# MACH_LOC_NUOC_KAROFI_V3_271015.net
KiCad netlist of a schematic drawn in Altium Designer
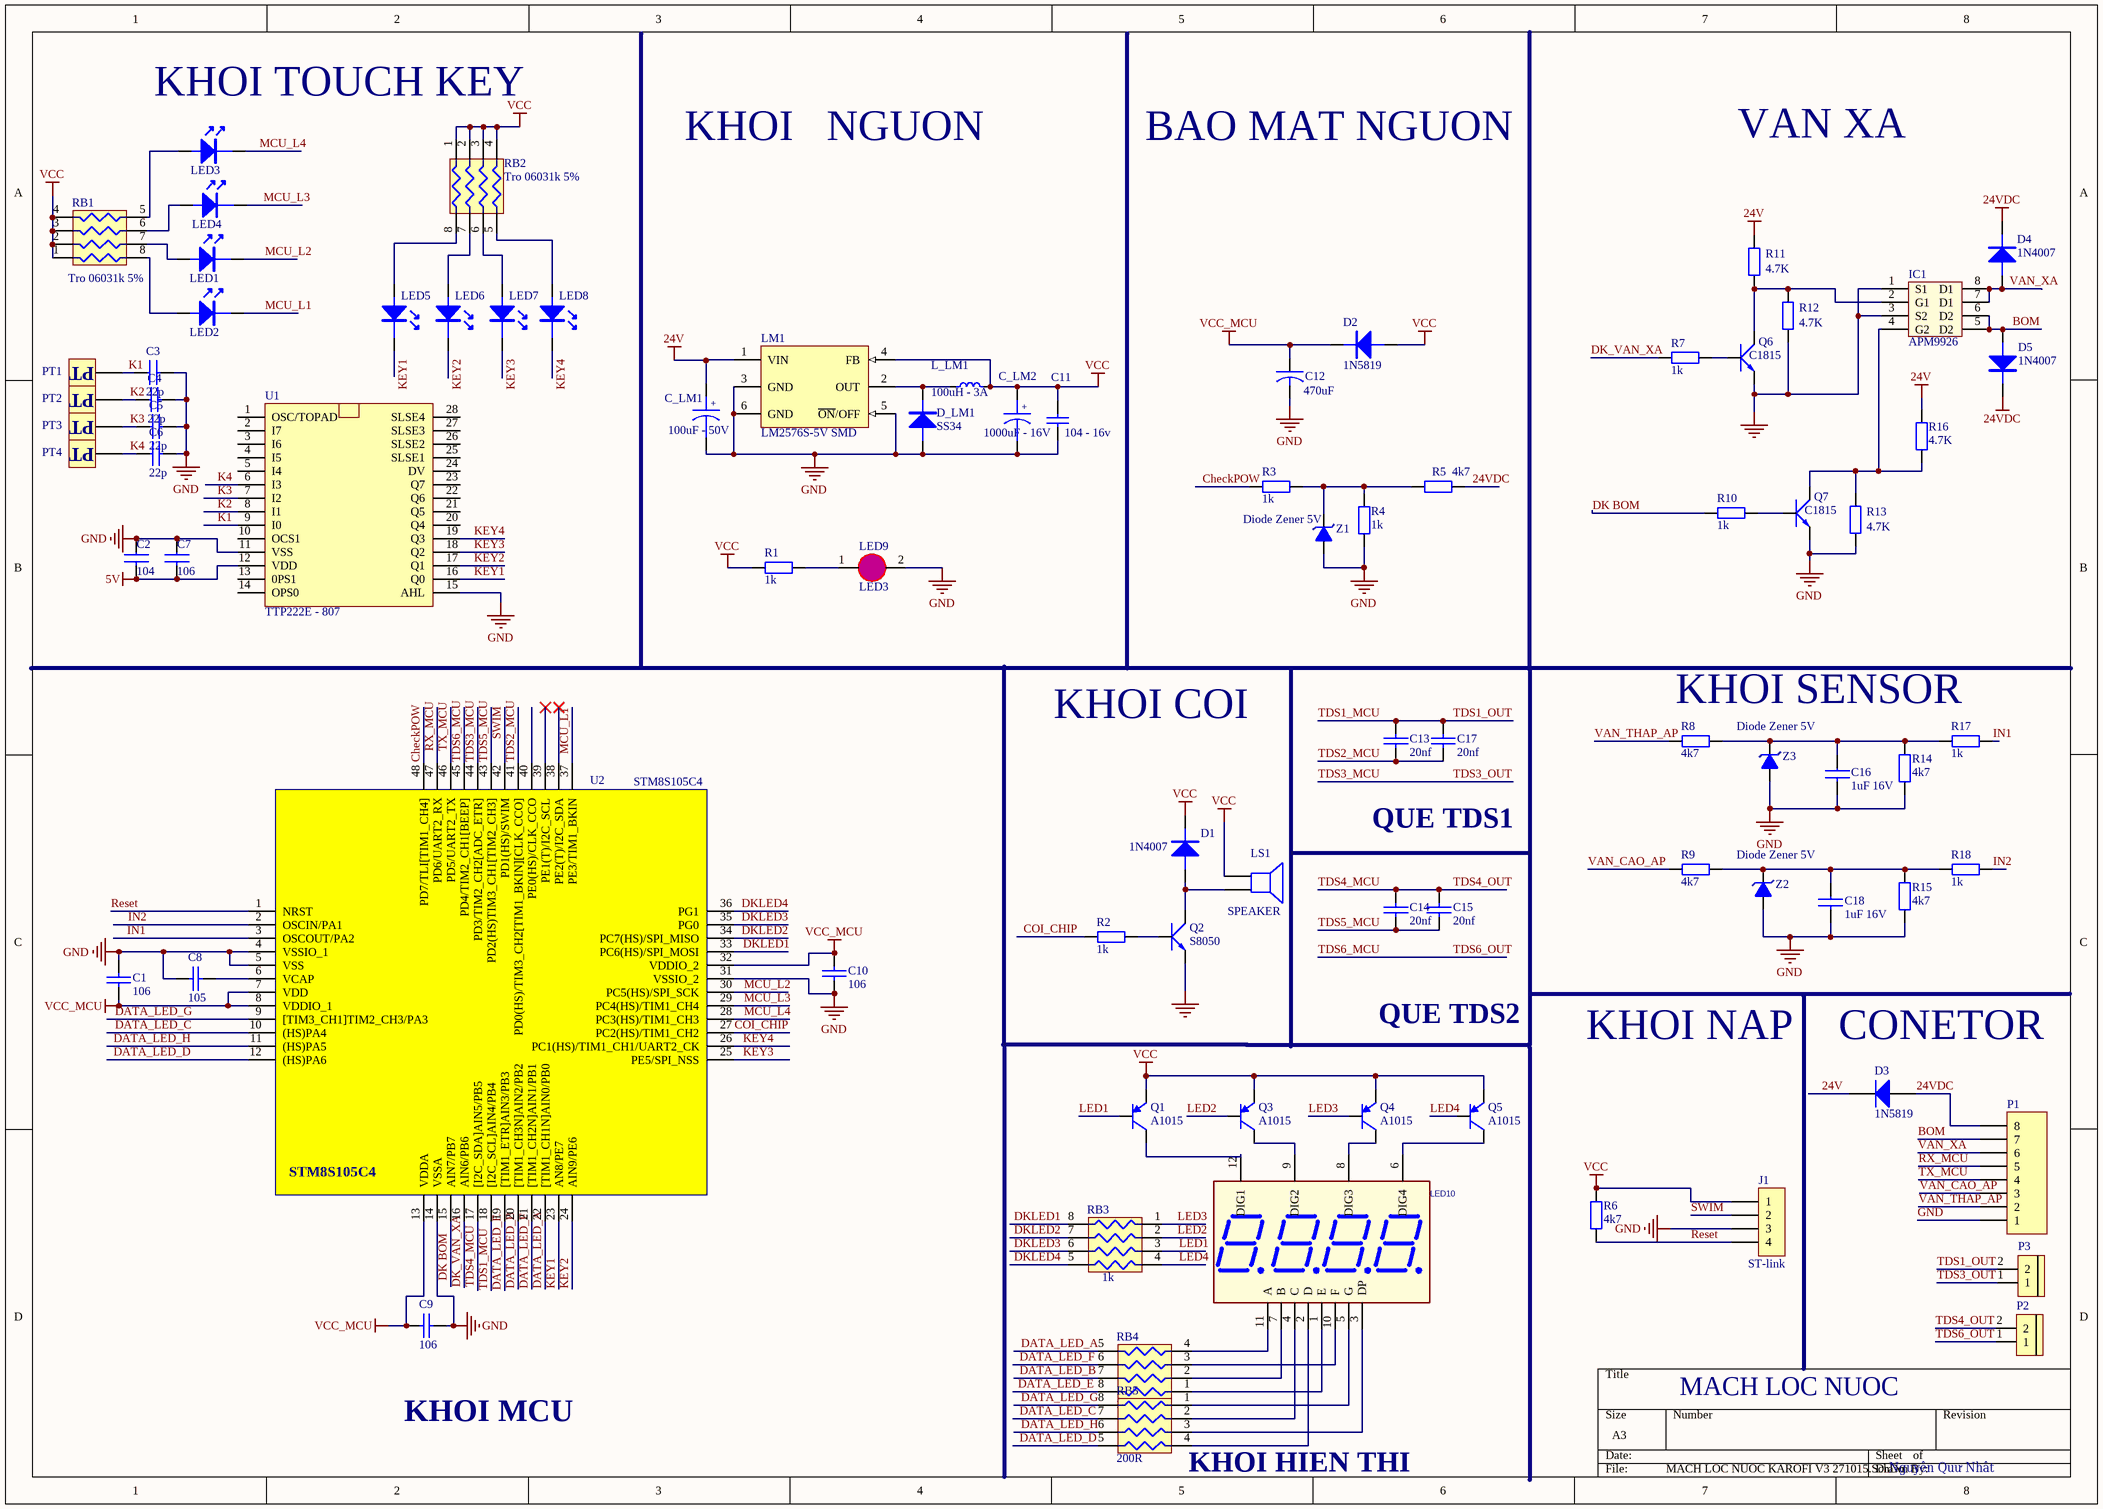
[diagram p0: MACH LOC NUOC KAROFI V3 271015.SchDoc]

(export (version "E")
  (design (tool "Eeschema 10.0.6"))
  (components
    (comp (ref "C1")
      (value "106")
      (footprint "Tu 0805")
      (description "Capacitor")
      (libsource (lib "Lib_Chuan_03_08_2013") (part "CAP"))
    )
    (comp (ref "C2")
      (value "Tu 0805 104")
      (footprint "Tu 0805")
      (fields (field (name "ALTIUM_UNNAMED_1") "104"))
      (libsource (lib "Cty") (part "CAP 0805"))
    )
    (comp (ref "C3")
      (value "Tu 0805 22p")
      (footprint "Tu 0805")
      (fields (field (name "ALTIUM_UNNAMED_1") "22p"))
      (libsource (lib "Cty") (part "CAP 0805"))
    )
    (comp (ref "C4")
      (value "Tu 0805 22p")
      (footprint "Tu 0805")
      (fields (field (name "ALTIUM_UNNAMED_1") "22p"))
      (libsource (lib "Cty") (part "CAP 0805"))
    )
    (comp (ref "C5")
      (value "Tu 0805 22p")
      (footprint "Tu 0805")
      (fields (field (name "ALTIUM_UNNAMED_1") "22p"))
      (libsource (lib "Cty") (part "CAP 0805"))
    )
    (comp (ref "C6")
      (value "Tu 0805 22p")
      (footprint "Tu 0805")
      (fields (field (name "ALTIUM_UNNAMED_1") "22p"))
      (libsource (lib "Cty") (part "CAP 0805"))
    )
    (comp (ref "C7")
      (value "Tu 0805 106")
      (footprint "Tu 0805")
      (fields (field (name "ALTIUM_UNNAMED_1") "106"))
      (libsource (lib "Cty") (part "CAP 0805"))
    )
    (comp (ref "C8")
      (value "105")
      (footprint "Tu 0805")
      (description "Capacitor")
      (libsource (lib "Lib_Chuan_03_08_2013") (part "CAP"))
    )
    (comp (ref "C9")
      (value "106")
      (footprint "Tu 0805")
      (description "Capacitor")
      (libsource (lib "Lib_Chuan_03_08_2013") (part "CAP"))
    )
    (comp (ref "C10")
      (value "106")
      (footprint "Tu 0805")
      (description "Capacitor")
      (libsource (lib "Lib_Chuan_03_08_2013") (part "CAP"))
    )
    (comp (ref "C11")
      (value "Tu 0805 1100nF (104)")
      (footprint "Tu 0805")
      (description "Capacitor (Semiconductor SIM Model)")
      (fields (field (name "ALTIUM_UNNAMED_1") "104 - 16v") (field (name "PUBLISHER") "Altium Limited"))
      (libsource (lib "Lib_Chuan_03_08_2013") (part "0805 104 - 50V"))
    )
    (comp (ref "C12")
      (value "Tu Hoa 470uF - 16V")
      (footprint "MH_THU VIEN CHUAN 13-03-2015 :CAP1000uF25V")
      (description "Capacitor")
      (fields (field (name "ALTIUM_UNNAMED_1") "470uF"))
      (libsource (lib "Board_Base") (part "CAPACITOR"))
    )
    (comp (ref "C13")
      (value "20nf")
      (footprint "Tu 0805")
      (description "Capacitor")
      (libsource (lib "Lib_Chuan_03_08_2013") (part "CAP"))
    )
    (comp (ref "C14")
      (value "20nf")
      (footprint "Tu 0805")
      (description "Capacitor")
      (libsource (lib "Lib_Chuan_03_08_2013") (part "CAP"))
    )
    (comp (ref "C15")
      (value "20nf")
      (footprint "Tu can Tantan 5.08")
      (description "Capacitor")
      (libsource (lib "Lib_Chuan_03_08_2013") (part "CAP"))
    )
    (comp (ref "C16") (value "1uF 16V") (footprint "Tu 0805") (libsource (lib "Cty") (part "CAP 0805")))
    (comp (ref "C17")
      (value "20nf")
      (footprint "Tu can Tantan 5.08")
      (description "Capacitor")
      (libsource (lib "Lib_Chuan_03_08_2013") (part "CAP"))
    )
    (comp (ref "C18") (value "1uF 16V") (footprint "Tu 0805") (libsource (lib "Cty") (part "CAP 0805")))
    (comp (ref "C_LM1")
      (value "Tu Nhom100uF - 50V")
      (footprint "Tu Nhom 100uF -50V")
      (description "Tu Hoa")
      (fields (field (name "ALTIUM_UNNAMED_1") "100uF - 50V"))
      (libsource (lib "Lib_Chuan_03_08_2013") (part "Tu Hoa"))
    )
    (comp (ref "C_LM2")
      (value "Tu Hoa 1000uF - 16V")
      (footprint "CAP 100uF-50V SMD")
      (description "Tu Hoa")
      (fields (field (name "ALTIUM_UNNAMED_1") "1000uF - 16V"))
      (libsource (lib "Lib_Chuan_03_08_2013") (part "Tu Hoa"))
    )
    (comp (ref "D1")
      (value "1N4007")
      (footprint "DO - SMB")
      (description "Diode")
      (libsource (lib "Sch_Library") (part "DIODE"))
    )
    (comp (ref "D2")
      (value "1N5819")
      (footprint "DO - SMB")
      (description "Diode")
      (libsource (lib "Sch_Library") (part "DIODE"))
    )
    (comp (ref "D3")
      (value "1N5819")
      (footprint "DO - SMB")
      (description "Diode Dan 1N5819")
      (fields (field (name "PUBLISHER") "Altium Limited"))
      (libsource (lib "Thu Vien Chuan MH") (part "Diode Dan 1N5819"))
    )
    (comp (ref "D4")
      (value "1N4007")
      (footprint "DO - SMB")
      (description "Diode")
      (libsource (lib "Sch_Library") (part "DIODE"))
    )
    (comp (ref "D5")
      (value "1N4007")
      (footprint "DO - SMB")
      (description "Diode")
      (libsource (lib "Sch_Library") (part "DIODE"))
    )
    (comp (ref "D_LM1")
      (value "Diode 1N5822 (SS34)")
      (footprint "DO - SMB")
      (fields (field (name "ALTIUM_UNNAMED_1") "SS34"))
      (libsource (lib "Lib_Chuan_03_08_2013") (part "DIODE"))
    )
    (comp (ref "IC1")
      (value "APM9926")
      (footprint "SO-8N")
      (description "Dual P-Channel Enhancement Mode MOSFET")
      (libsource (lib "MH_THU VIEN CHUAN 12-03-2015") (part "APM4953"))
    )
    (comp (ref "J1")
      (value "ST-link")
      (footprint "MH_THU VIEN CHUAN 13-03-2015 :HDR1X4")
      (description "Connector")
      (libsource (lib "Lib_Chuan_02_08_2013") (part "CON4"))
    )
    (comp (ref "LED1")
      (value "LED 0805 Do SMD")
      (footprint "LED0805_MH")
      (libsource (lib "Board_Base") (part "LED"))
    )
    (comp (ref "LED2")
      (value "LED 0805 Do SMD")
      (footprint "LED0805_MH")
      (libsource (lib "Board_Base") (part "LED"))
    )
    (comp (ref "LED3")
      (value "LED 0805 Do SMD")
      (footprint "LED0805_MH")
      (libsource (lib "Board_Base") (part "LED"))
    )
    (comp (ref "LED4")
      (value "LED 0805 Do SMD")
      (footprint "LED0805_MH")
      (libsource (lib "Board_Base") (part "LED"))
    )
    (comp (ref "LED5")
      (value "LED 0805 Do SMD")
      (footprint "LED0805_MH")
      (libsource (lib "Board_Base") (part "LED"))
    )
    (comp (ref "LED6")
      (value "LED 0805 Do SMD")
      (footprint "LED0805_MH")
      (libsource (lib "Board_Base") (part "LED"))
    )
    (comp (ref "LED7")
      (value "LED 0805 Do SMD")
      (footprint "LED0805_MH")
      (libsource (lib "Board_Base") (part "LED"))
    )
    (comp (ref "LED8")
      (value "LED 0805 Do SMD")
      (footprint "LED0805_MH")
      (libsource (lib "Board_Base") (part "LED"))
    )
    (comp (ref "LED9")
      (value "LED3")
      (footprint "LED0805_MH")
      (description "LED 3mm")
      (libsource (lib "MH_THU VIEN CHUAN 01-11-2014") (part "LEDSMD"))
    )
    (comp (ref "LED10")
      (value "LED7SEG4DIGIT")
      (footprint "LED7seg4")
      (libsource (lib "Lib_Chuan_03_08_2013") (part "LED7SEG4DIGIT"))
    )
    (comp (ref "LM1")
      (value "LM2576S-5V SMD")
      (footprint "TO263-5")
      (fields
        (field (name "PARTNUMBER") "LM2576T-5.0")
        (field (name "MANUFACTURER") "National Semiconductor")
        (field (name "DIGIKEYPARTNUMBER") "LM2576T-5.0-ND")
        (field (name "PUBLISHER") "Altium Limited")
      )
      (libsource (lib "Lib_Chuan_03_08_2013") (part "LM2576.xxV"))
    )
    (comp (ref "LS1")
      (value "SPEAKER")
      (footprint "SPEAKER")
      (libsource (lib "Sch_Library") (part "SPEAKER"))
    )
    (comp (ref "L_LM1")
      (value "Cuon Cam 100uH 3A")
      (footprint "L100uH3A")
      (fields (field (name "ALTIUM_UNNAMED_1") "100uH - 3A"))
      (libsource (lib "Lib_Chuan_03_08_2013") (part "Cuon Cam 100uH 3A"))
    )
    (comp (ref "P1")
      (value "Header 8")
      (footprint "Header 8P 2.54 Duc Cong")
      (description "Header, 8-Pin")
      (fields (field (name "PUBLISHER") "Altium Limited"))
      (libsource (lib "MH_THU VIEN CHUAN 12-03-2015") (part "Header 8"))
    )
    (comp (ref "P2")
      (value "Header 2")
      (footprint "Header 2 Duc Cong 2.54")
      (description "Big Header 2")
      (libsource (lib "MH_THU VIEN CHUAN 01-11-2014") (part "Header 2"))
    )
    (comp (ref "P3")
      (value "Header 2")
      (footprint "Header 2 Duc Cong 2.54")
      (description "Big Header 2")
      (libsource (lib "MH_THU VIEN CHUAN 01-11-2014") (part "Header 2"))
    )
    (comp (ref "PT1")
      (value "PAD TOUCH")
      (footprint "PAD TOUCH")
      (libsource (lib "MH_THU VIEN CHUAN 01-11-2014") (part "PAD TOUCH"))
    )
    (comp (ref "PT2")
      (value "PAD TOUCH")
      (footprint "PAD TOUCH")
      (libsource (lib "MH_THU VIEN CHUAN 01-11-2014") (part "PAD TOUCH"))
    )
    (comp (ref "PT3")
      (value "PAD TOUCH")
      (footprint "PAD TOUCH")
      (libsource (lib "MH_THU VIEN CHUAN 01-11-2014") (part "PAD TOUCH"))
    )
    (comp (ref "PT4")
      (value "PAD TOUCH")
      (footprint "PAD TOUCH")
      (libsource (lib "MH_THU VIEN CHUAN 01-11-2014") (part "PAD TOUCH"))
    )
    (comp (ref "Q1")
      (value "A1015")
      (footprint "SOT23B")
      (description "PNP General Purpose Amplifier")
      (fields (field (name "PUBLISHER") "Altium Limited"))
      (libsource (lib "MH_THU VIEN CHUAN 01-11-2014") (part "2SA1015"))
    )
    (comp (ref "Q2")
      (value "S8050")
      (footprint "SOT23B")
      (description "NPN 600mW, ECB")
      (libsource (lib "MH_THU VIEN CHUAN 01-11-2014") (part "C1815"))
    )
    (comp (ref "Q3")
      (value "A1015")
      (footprint "SOT23B")
      (description "PNP General Purpose Amplifier")
      (fields (field (name "PUBLISHER") "Altium Limited"))
      (libsource (lib "MH_THU VIEN CHUAN 01-11-2014") (part "2SA1015"))
    )
    (comp (ref "Q4")
      (value "A1015")
      (footprint "SOT23B")
      (description "PNP General Purpose Amplifier")
      (fields (field (name "PUBLISHER") "Altium Limited"))
      (libsource (lib "MH_THU VIEN CHUAN 01-11-2014") (part "2SA1015"))
    )
    (comp (ref "Q5")
      (value "A1015")
      (footprint "SOT23B")
      (description "PNP General Purpose Amplifier")
      (fields (field (name "PUBLISHER") "Altium Limited"))
      (libsource (lib "MH_THU VIEN CHUAN 01-11-2014") (part "2SA1015"))
    )
    (comp (ref "Q6")
      (value "C1815")
      (footprint "SOT23B")
      (description "NPN 600mW, ECB")
      (libsource (lib "MH_THU VIEN CHUAN 01-11-2014") (part "C1815"))
    )
    (comp (ref "Q7")
      (value "C1815")
      (footprint "SOT23B")
      (description "NPN 600mW, ECB")
      (libsource (lib "MH_THU VIEN CHUAN 01-11-2014") (part "C1815"))
    )
    (comp (ref "R1")
      (value "1k")
      (footprint "Tro SMD 0805")
      (description "Tro 0805")
      (fields (field (name "Comment") "Tro 0805 1k"))
      (libsource (lib "MH_THU VIEN CHUAN 01-11-2014") (part "Tro 0805"))
    )
    (comp (ref "R2")
      (value "1k")
      (footprint "Tro SMD 0805")
      (description "Tro 0805")
      (fields (field (name "Comment") "Tro 0805 1k"))
      (libsource (lib "MH_THU VIEN CHUAN 01-11-2014") (part "Tro 0805"))
    )
    (comp (ref "R3")
      (value "1k")
      (footprint "Tro SMD 0805")
      (description "Tro 0805")
      (fields (field (name "Comment") "Tro 0805 1k"))
      (libsource (lib "MH_THU VIEN CHUAN 01-11-2014") (part "Tro 0805"))
    )
    (comp (ref "R4")
      (value "1k")
      (footprint "Tro SMD 0805")
      (description "Tro 0805")
      (fields (field (name "Comment") "Tro 0805 4k7 5%"))
      (libsource (lib "MH_THU VIEN CHUAN 01-11-2014") (part "Tro 0805"))
    )
    (comp (ref "R5")
      (value "4k7")
      (footprint "Tro SMD 0805")
      (description "Tro 0805")
      (fields (field (name "Comment") "Tro 0805 4k7 5%"))
      (libsource (lib "MH_THU VIEN CHUAN 01-11-2014") (part "Tro 0805"))
    )
    (comp (ref "R6")
      (value "4k7")
      (footprint "Tro SMD 0805")
      (description "Tro 0805")
      (fields (field (name "Comment") "Tro 0805 4k7 5%"))
      (libsource (lib "MH_THU VIEN CHUAN 01-11-2014") (part "Tro 0805"))
    )
    (comp (ref "R7")
      (value "1k")
      (footprint "Tro SMD 0805")
      (description "Tro 0805")
      (fields (field (name "Comment") "Tro 0805 1k"))
      (libsource (lib "MH_THU VIEN CHUAN 01-11-2014") (part "Tro 0805"))
    )
    (comp (ref "R8")
      (value "4k7")
      (footprint "Tro SMD 0805")
      (description "Tro 0805")
      (fields (field (name "Comment") "Tro 0805 4k7 5%"))
      (libsource (lib "MH_THU VIEN CHUAN 01-11-2014") (part "Tro 0805"))
    )
    (comp (ref "R9")
      (value "4k7")
      (footprint "Tro SMD 0805")
      (description "Tro 0805")
      (fields (field (name "Comment") "Tro 0805 4k7 5%"))
      (libsource (lib "MH_THU VIEN CHUAN 01-11-2014") (part "Tro 0805"))
    )
    (comp (ref "R10")
      (value "1k")
      (footprint "Tro SMD 0805")
      (description "Tro 0805")
      (fields (field (name "Comment") "Tro 0805 1k"))
      (libsource (lib "MH_THU VIEN CHUAN 01-11-2014") (part "Tro 0805"))
    )
    (comp (ref "R11")
      (value "4.7K")
      (footprint "Tro SMD 0805")
      (description "Tro 0805")
      (fields (field (name "Comment") "Tro 0805 4.7K"))
      (libsource (lib "MH_THU VIEN CHUAN 01-11-2014") (part "Tro 0805"))
    )
    (comp (ref "R12")
      (value "4.7K")
      (footprint "Tro SMD 0805")
      (description "Tro 0805")
      (fields (field (name "Comment") "Tro 0805 4.7K"))
      (libsource (lib "MH_THU VIEN CHUAN 01-11-2014") (part "Tro 0805"))
    )
    (comp (ref "R13")
      (value "4.7K")
      (footprint "Tro SMD 0805")
      (description "Tro 0805")
      (fields (field (name "Comment") "Tro 0805 4.7K"))
      (libsource (lib "MH_THU VIEN CHUAN 01-11-2014") (part "Tro 0805"))
    )
    (comp (ref "R14")
      (value "4k7")
      (footprint "Tro SMD 0805")
      (description "Tro 0805")
      (fields (field (name "Comment") "Tro 0805 4k7 5%"))
      (libsource (lib "MH_THU VIEN CHUAN 01-11-2014") (part "Tro 0805"))
    )
    (comp (ref "R15")
      (value "4k7")
      (footprint "Tro SMD 0805")
      (description "Tro 0805")
      (fields (field (name "Comment") "Tro 0805 4k7 5%"))
      (libsource (lib "MH_THU VIEN CHUAN 01-11-2014") (part "Tro 0805"))
    )
    (comp (ref "R16")
      (value "4.7K")
      (footprint "Tro SMD 0805")
      (description "Tro 0805")
      (fields (field (name "Comment") "Tro 0805 4.7K"))
      (libsource (lib "MH_THU VIEN CHUAN 01-11-2014") (part "Tro 0805"))
    )
    (comp (ref "R17")
      (value "1k")
      (footprint "Tro SMD 0805")
      (description "Tro 0805")
      (fields (field (name "Comment") "Tro 0805 1k"))
      (libsource (lib "MH_THU VIEN CHUAN 01-11-2014") (part "Tro 0805"))
    )
    (comp (ref "R18")
      (value "1k")
      (footprint "Tro SMD 0805")
      (description "Tro 0805")
      (fields (field (name "Comment") "Tro 0805 1k"))
      (libsource (lib "MH_THU VIEN CHUAN 01-11-2014") (part "Tro 0805"))
    )
    (comp (ref "RB1")
      (value "Tro 06031k 5%")
      (footprint "Tro Bang 4 0603")
      (description "Tro Bang 0603")
      (libsource (lib "MH_THU VIEN CHUAN 12-03-2015") (part "Tro Bang 0603"))
    )
    (comp (ref "RB2")
      (value "Tro 06031k 5%")
      (footprint "Tro Bang 4 0603")
      (description "Tro Bang 0603")
      (libsource (lib "") (part "Tro Bang 0603_1"))
    )
    (comp (ref "RB3")
      (value "Tro 06031k 5%")
      (footprint "Tro Bang 4 0603")
      (description "Tro Bang 0603")
      (fields (field (name "ALTIUM_UNNAMED_1") "1k"))
      (libsource (lib "MH_THU VIEN CHUAN 01-11-2014") (part "Tro Bang 0603"))
    )
    (comp (ref "RB4")
      (value "Tro 0603 200R 5%")
      (footprint "Tro Bang 4 0603")
      (description "Tro Bang 0603")
      (fields (field (name "ALTIUM_UNNAMED_1") "200R"))
      (libsource (lib "") (part "Tro Bang 0603_1"))
    )
    (comp (ref "RB5")
      (value "Tro 0603 200R 5%")
      (footprint "Tro Bang 4 0603")
      (description "Tro Bang 0603")
      (fields (field (name "ALTIUM_UNNAMED_1") "200R"))
      (libsource (lib "MH_THU VIEN CHUAN 01-11-2014") (part "Tro Bang 0603"))
    )
    (comp (ref "U1")
      (value "TTP222E - 807")
      (footprint "TSSOP28")
      (libsource (lib "MH_THU VIEN CHUAN 01-11-2014") (part "TTP222E"))
    )
    (comp (ref "U2")
      (value "STM8S105C4")
      (footprint "48A_M")
      (libsource (lib "Lib_Chuan_03_08_2013") (part "STM8S105C4"))
    )
    (comp (ref "Z1")
      (value "Diode Zener 5V")
      (footprint "ZENNER SMD")
      (description "Diode  Zener")
      (libsource (lib "Cty") (part "Diode Zener"))
    )
    (comp (ref "Z2")
      (value "Diode Zener 5V")
      (footprint "ZENNER SMD")
      (description "Diode  Zener")
      (libsource (lib "Cty") (part "Diode Zener"))
    )
    (comp (ref "Z3")
      (value "Diode Zener 5V")
      (footprint "ZENNER SMD")
      (description "Diode  Zener")
      (libsource (lib "Cty") (part "Diode Zener"))
    )
  )
  (nets
    (net (code "1") (name "/BOM") (class "Default")
      (node (ref "D5") (pin "1") (pinfunction "1_1") (pintype "passive"))
      (node (ref "IC1") (pin "5") (pinfunction "D2_5") (pintype "passive"))
      (node (ref "IC1") (pin "6") (pinfunction "D2_6") (pintype "passive"))
      (node (ref "P1") (pin "7") (pinfunction "7_7") (pintype "passive"))
    )
    (net (code "2") (name "/COI_CHIP") (class "Default")
      (node (ref "R2") (pin "2") (pinfunction "2_2") (pintype "passive"))
      (node (ref "U2") (pin "27") (pinfunction "PC2(HS)/TIM1_CH2_27") (pintype "passive"))
    )
    (net (code "3") (name "/CheckPOW") (class "Default")
      (node (ref "R3") (pin "2") (pinfunction "2_2") (pintype "passive"))
      (node (ref "U2") (pin "48") (pinfunction "PD7/TLI[TIM1_CH4]_48") (pintype "passive"))
    )
    (net (code "4") (name "/DATA_LED_A") (class "Default")
      (node (ref "RB4") (pin "5") (pintype "passive"))
      (node (ref "U2") (pin "22") (pinfunction "[TIM1_CH1N]AIN0/PB0_22") (pintype "passive"))
    )
    (net (code "5") (name "/DATA_LED_B") (class "Default")
      (node (ref "RB4") (pin "7") (pintype "passive"))
      (node (ref "U2") (pin "20") (pinfunction "[TIM1_CH3N]AIN2/PB2_20") (pintype "passive"))
    )
    (net (code "6") (name "/DATA_LED_C") (class "Default")
      (node (ref "RB5") (pin "7") (pintype "passive"))
      (node (ref "U2") (pin "10") (pinfunction "(HS)PA4_10") (pintype "passive"))
    )
    (net (code "7") (name "/DATA_LED_D") (class "Default")
      (node (ref "RB5") (pin "5") (pintype "passive"))
      (node (ref "U2") (pin "12") (pinfunction "(HS)PA6_12") (pintype "passive"))
    )
    (net (code "8") (name "/DATA_LED_E") (class "Default")
      (node (ref "RB4") (pin "8") (pintype "passive"))
      (node (ref "U2") (pin "19") (pinfunction "[TIM1_ETR]AIN3/PB3_19") (pintype "passive"))
    )
    (net (code "9") (name "/DATA_LED_F") (class "Default")
      (node (ref "RB4") (pin "6") (pintype "passive"))
      (node (ref "U2") (pin "21") (pinfunction "[TIM1_CH2N]AIN1/PB1_21") (pintype "passive"))
    )
    (net (code "10") (name "/DATA_LED_G") (class "Default")
      (node (ref "RB5") (pin "8") (pintype "passive"))
      (node (ref "U2") (pin "9") (pinfunction "[TIM3_CH1]TIM2_CH3/PA3_9") (pintype "passive"))
    )
    (net (code "11") (name "/DATA_LED_H") (class "Default")
      (node (ref "RB5") (pin "6") (pintype "passive"))
      (node (ref "U2") (pin "11") (pinfunction "(HS)PA5_11") (pintype "passive"))
    )
    (net (code "12") (name "/DK BOM") (class "Default")
      (node (ref "R10") (pin "2") (pinfunction "2_2") (pintype "passive"))
      (node (ref "U2") (pin "15") (pinfunction "AIN7/PB7_15") (pintype "passive"))
    )
    (net (code "13") (name "/DKLED1") (class "Default")
      (node (ref "RB3") (pin "8") (pintype "passive"))
      (node (ref "U2") (pin "33") (pinfunction "PC6(HS)/SPI_MOSI_33") (pintype "passive"))
    )
    (net (code "14") (name "/DKLED2") (class "Default")
      (node (ref "RB3") (pin "7") (pintype "passive"))
      (node (ref "U2") (pin "34") (pinfunction "PC7(HS)/SPI_MISO_34") (pintype "passive"))
    )
    (net (code "15") (name "/DKLED3") (class "Default")
      (node (ref "RB3") (pin "6") (pintype "passive"))
      (node (ref "U2") (pin "35") (pinfunction "PG0_35") (pintype "passive"))
    )
    (net (code "16") (name "/DKLED4") (class "Default")
      (node (ref "RB3") (pin "5") (pintype "passive"))
      (node (ref "U2") (pin "36") (pinfunction "PG1_36") (pintype "passive"))
    )
    (net (code "17") (name "/DK_VAN_XA") (class "Default")
      (node (ref "R7") (pin "2") (pinfunction "2_2") (pintype "passive"))
      (node (ref "U2") (pin "16") (pinfunction "AIN6/PB6_16") (pintype "passive"))
    )
    (net (code "18") (name "/IN1") (class "Default")
      (node (ref "R17") (pin "1") (pinfunction "1_1") (pintype "passive"))
      (node (ref "U2") (pin "3") (pinfunction "OSCOUT/PA2_3") (pintype "passive"))
    )
    (net (code "19") (name "/IN2") (class "Default")
      (node (ref "R18") (pin "1") (pinfunction "1_1") (pintype "passive"))
      (node (ref "U2") (pin "2") (pinfunction "OSCIN/PA1_2") (pintype "passive"))
    )
    (net (code "20") (name "/K1") (class "Default")
      (node (ref "C3") (pin "1") (pinfunction "1_1") (pintype "passive"))
      (node (ref "PT1") (pin "1") (pinfunction "1_1") (pintype "passive"))
      (node (ref "U1") (pin "9") (pinfunction "I0_9") (pintype "passive"))
    )
    (net (code "21") (name "/K2") (class "Default")
      (node (ref "C4") (pin "1") (pinfunction "1_1") (pintype "passive"))
      (node (ref "PT2") (pin "1") (pinfunction "1_1") (pintype "passive"))
      (node (ref "U1") (pin "8") (pinfunction "I1_8") (pintype "passive"))
    )
    (net (code "22") (name "/K3") (class "Default")
      (node (ref "C5") (pin "1") (pinfunction "1_1") (pintype "passive"))
      (node (ref "PT3") (pin "1") (pinfunction "1_1") (pintype "passive"))
      (node (ref "U1") (pin "7") (pinfunction "I2_7") (pintype "passive"))
    )
    (net (code "23") (name "/K4") (class "Default")
      (node (ref "C6") (pin "1") (pinfunction "1_1") (pintype "passive"))
      (node (ref "PT4") (pin "1") (pinfunction "1_1") (pintype "passive"))
      (node (ref "U1") (pin "6") (pinfunction "I3_6") (pintype "passive"))
    )
    (net (code "24") (name "/KEY1") (class "Default")
      (node (ref "LED5") (pin "2") (pinfunction "2_2") (pintype "passive"))
      (node (ref "U1") (pin "16") (pinfunction "Q0_16") (pintype "passive"))
      (node (ref "U2") (pin "23") (pinfunction "AN8/PE7_23") (pintype "passive"))
    )
    (net (code "25") (name "/KEY2") (class "Default")
      (node (ref "LED6") (pin "2") (pinfunction "2_2") (pintype "passive"))
      (node (ref "U1") (pin "17") (pinfunction "Q1_17") (pintype "passive"))
      (node (ref "U2") (pin "24") (pinfunction "AIN9/PE6_24") (pintype "passive"))
    )
    (net (code "26") (name "/KEY3") (class "Default")
      (node (ref "LED7") (pin "2") (pinfunction "2_2") (pintype "passive"))
      (node (ref "U1") (pin "18") (pinfunction "Q2_18") (pintype "passive"))
      (node (ref "U2") (pin "25") (pinfunction "PE5/SPI_NSS_25") (pintype "passive"))
    )
    (net (code "27") (name "/KEY4") (class "Default")
      (node (ref "LED8") (pin "2") (pinfunction "2_2") (pintype "passive"))
      (node (ref "U1") (pin "19") (pinfunction "Q3_19") (pintype "passive"))
      (node (ref "U2") (pin "26") (pinfunction "PC1(HS)/TIM1_CH1/UART2_CK_26") (pintype "passive"))
    )
    (net (code "28") (name "/LED1") (class "Default")
      (node (ref "Q1") (pin "1") (pinfunction "B_1") (pintype "passive"))
      (node (ref "RB3") (pin "3") (pintype "passive"))
    )
    (net (code "29") (name "/LED2") (class "Default")
      (node (ref "Q3") (pin "1") (pinfunction "B_1") (pintype "passive"))
      (node (ref "RB3") (pin "2") (pintype "passive"))
    )
    (net (code "30") (name "/LED3") (class "Default")
      (node (ref "Q4") (pin "1") (pinfunction "B_1") (pintype "passive"))
      (node (ref "RB3") (pin "1") (pintype "passive"))
    )
    (net (code "31") (name "/LED4") (class "Default")
      (node (ref "Q5") (pin "1") (pinfunction "B_1") (pintype "passive"))
      (node (ref "RB3") (pin "4") (pintype "passive"))
    )
    (net (code "32") (name "/MCU_L1") (class "Default")
      (node (ref "LED2") (pin "2") (pinfunction "2_2") (pintype "passive"))
      (node (ref "U2") (pin "37") (pinfunction "PE3/TIM1_BKIN_37") (pintype "passive"))
    )
    (net (code "33") (name "/MCU_L2") (class "Default")
      (node (ref "LED1") (pin "2") (pinfunction "2_2") (pintype "passive"))
      (node (ref "U2") (pin "30") (pinfunction "PC5(HS)/SPI_SCK_30") (pintype "passive"))
    )
    (net (code "34") (name "/MCU_L3") (class "Default")
      (node (ref "LED4") (pin "2") (pinfunction "2_2") (pintype "passive"))
      (node (ref "U2") (pin "29") (pinfunction "PC4(HS)/TIM1_CH4_29") (pintype "passive"))
    )
    (net (code "35") (name "/MCU_L4") (class "Default")
      (node (ref "LED3") (pin "2") (pinfunction "2_2") (pintype "passive"))
      (node (ref "U2") (pin "28") (pinfunction "PC3(HS)/TIM1_CH3_28") (pintype "passive"))
    )
    (net (code "36") (name "/RX_MCU") (class "Default")
      (node (ref "P1") (pin "5") (pinfunction "5_5") (pintype "passive"))
      (node (ref "U2") (pin "47") (pinfunction "PD6/UART2_RX_47") (pintype "passive"))
    )
    (net (code "37") (name "/Reset") (class "Default")
      (node (ref "J1") (pin "4") (pinfunction "4_4") (pintype "passive"))
      (node (ref "R6") (pin "2") (pinfunction "2_2") (pintype "passive"))
      (node (ref "U2") (pin "1") (pinfunction "NRST_1") (pintype "passive"))
    )
    (net (code "38") (name "/SWIM") (class "Default")
      (node (ref "J1") (pin "2") (pinfunction "2_2") (pintype "passive"))
      (node (ref "U2") (pin "42") (pinfunction "PD1(HS)/SWIM_42") (pintype "passive"))
    )
    (net (code "39") (name "/TDS1_MCU") (class "Default")
      (node (ref "C13") (pin "2") (pinfunction "2_2") (pintype "passive"))
      (node (ref "C17") (pin "2") (pinfunction "2_2") (pintype "passive"))
      (node (ref "P3") (pin "2") (pinfunction "2_2") (pintype "passive"))
      (node (ref "U2") (pin "18") (pinfunction "[I2C_SCL]AIN4/PB4_18") (pintype "passive"))
    )
    (net (code "40") (name "/TDS2_MCU") (class "Default")
      (node (ref "C13") (pin "1") (pinfunction "1_1") (pintype "passive"))
      (node (ref "C17") (pin "1") (pinfunction "1_1") (pintype "passive"))
      (node (ref "U2") (pin "41") (pinfunction "PD0(HS)/TIM3_CH2[TIM1_BKIN][CLK_CCO]_41") (pintype "passive"))
    )
    (net (code "41") (name "/TDS3_MCU") (class "Default")
      (node (ref "P3") (pin "1") (pinfunction "1_1") (pintype "passive"))
      (node (ref "U2") (pin "44") (pinfunction "PD3/TIM2_CH2[ADC_ETR]_44") (pintype "passive"))
    )
    (net (code "42") (name "/TDS4_MCU") (class "Default")
      (node (ref "C14") (pin "2") (pinfunction "2_2") (pintype "passive"))
      (node (ref "C15") (pin "2") (pinfunction "2_2") (pintype "passive"))
      (node (ref "P2") (pin "2") (pinfunction "2_2") (pintype "passive"))
      (node (ref "U2") (pin "17") (pinfunction "[I2C_SDA]AIN5/PB5_17") (pintype "passive"))
    )
    (net (code "43") (name "/TDS5_MCU") (class "Default")
      (node (ref "C14") (pin "1") (pinfunction "1_1") (pintype "passive"))
      (node (ref "C15") (pin "1") (pinfunction "1_1") (pintype "passive"))
      (node (ref "U2") (pin "43") (pinfunction "PD2(HS)TIM3_CH1[TIM2_CH3]_43") (pintype "passive"))
    )
    (net (code "44") (name "/TDS6_MCU") (class "Default")
      (node (ref "P2") (pin "1") (pinfunction "1_1") (pintype "passive"))
      (node (ref "U2") (pin "45") (pinfunction "PD4/TIM2_CH1[BEEP]_45") (pintype "passive"))
    )
    (net (code "45") (name "/TX_MCU") (class "Default")
      (node (ref "P1") (pin "4") (pinfunction "4_4") (pintype "passive"))
      (node (ref "U2") (pin "46") (pinfunction "PD5/UART2_TX_46") (pintype "passive"))
    )
    (net (code "46") (name "/VAN_CAO_AP") (class "Default")
      (node (ref "P1") (pin "3") (pinfunction "3_3") (pintype "passive"))
      (node (ref "R9") (pin "1") (pinfunction "1_1") (pintype "passive"))
    )
    (net (code "47") (name "/VAN_THAP_AP") (class "Default")
      (node (ref "P1") (pin "2") (pinfunction "2_2") (pintype "passive"))
      (node (ref "R8") (pin "1") (pinfunction "1_1") (pintype "passive"))
    )
    (net (code "48") (name "/VAN_XA") (class "Default")
      (node (ref "D4") (pin "1") (pinfunction "1_1") (pintype "passive"))
      (node (ref "IC1") (pin "7") (pinfunction "D1_7") (pintype "passive"))
      (node (ref "IC1") (pin "8") (pinfunction "D1_8") (pintype "passive"))
      (node (ref "P1") (pin "6") (pinfunction "6_6") (pintype "passive"))
    )
    (net (code "49") (name "5V") (class "Default")
      (node (ref "C2") (pin "2") (pinfunction "2_2") (pintype "passive"))
      (node (ref "C7") (pin "2") (pinfunction "2_2") (pintype "passive"))
      (node (ref "U1") (pin "12") (pinfunction "VDD_12") (pintype "passive"))
    )
    (net (code "50") (name "24V") (class "Default")
      (node (ref "C_LM1") (pin "1") (pinfunction "1_1") (pintype "passive"))
      (node (ref "D3") (pin "2") (pinfunction "K_2") (pintype "passive"))
      (node (ref "LM1") (pin "1") (pinfunction "VIN_1") (pintype "power_in"))
      (node (ref "R11") (pin "1") (pinfunction "1_1") (pintype "passive"))
      (node (ref "R16") (pin "2") (pinfunction "2_2") (pintype "passive"))
    )
    (net (code "51") (name "24VDC") (class "Default")
      (node (ref "D3") (pin "1") (pinfunction "A_1") (pintype "passive"))
      (node (ref "D4") (pin "2") (pinfunction "2_2") (pintype "passive"))
      (node (ref "D5") (pin "2") (pinfunction "2_2") (pintype "passive"))
      (node (ref "P1") (pin "8") (pinfunction "8_8") (pintype "passive"))
      (node (ref "R5") (pin "2") (pinfunction "2_2") (pintype "passive"))
    )
    (net (code "52") (name "GND") (class "Default")
      (node (ref "C1") (pin "1") (pinfunction "1_1") (pintype "passive"))
      (node (ref "C10") (pin "2") (pinfunction "2_2") (pintype "passive"))
      (node (ref "C11") (pin "1") (pintype "passive"))
      (node (ref "C12") (pin "2") (pinfunction "2_2") (pintype "passive"))
      (node (ref "C16") (pin "2") (pinfunction "2_2") (pintype "passive"))
      (node (ref "C18") (pin "2") (pinfunction "2_2") (pintype "passive"))
      (node (ref "C2") (pin "1") (pinfunction "1_1") (pintype "passive"))
      (node (ref "C3") (pin "2") (pinfunction "2_2") (pintype "passive"))
      (node (ref "C4") (pin "2") (pinfunction "2_2") (pintype "passive"))
      (node (ref "C5") (pin "2") (pinfunction "2_2") (pintype "passive"))
      (node (ref "C6") (pin "2") (pinfunction "2_2") (pintype "passive"))
      (node (ref "C7") (pin "1") (pinfunction "1_1") (pintype "passive"))
      (node (ref "C8") (pin "1") (pinfunction "1_1") (pintype "passive"))
      (node (ref "C9") (pin "2") (pinfunction "2_2") (pintype "passive"))
      (node (ref "C_LM1") (pin "2") (pinfunction "2_2") (pintype "passive"))
      (node (ref "C_LM2") (pin "2") (pinfunction "2_2") (pintype "passive"))
      (node (ref "D_LM1") (pin "1") (pinfunction "1_1") (pintype "passive"))
      (node (ref "IC1") (pin "1") (pinfunction "S1_1") (pintype "passive"))
      (node (ref "IC1") (pin "3") (pinfunction "S2_3") (pintype "passive"))
      (node (ref "J1") (pin "3") (pinfunction "3_3") (pintype "passive"))
      (node (ref "LED9") (pin "2") (pinfunction "K_2") (pintype "passive"))
      (node (ref "LM1") (pin "3") (pinfunction "GND_3") (pintype "power_in"))
      (node (ref "LM1") (pin "5") (pinfunction "~{ON}/OFF_5") (pintype "input"))
      (node (ref "LM1") (pin "6") (pinfunction "GND_6") (pintype "passive"))
      (node (ref "P1") (pin "1") (pinfunction "1_1") (pintype "passive"))
      (node (ref "Q2") (pin "3") (pinfunction "E_3") (pintype "passive"))
      (node (ref "Q6") (pin "3") (pinfunction "E_3") (pintype "passive"))
      (node (ref "Q7") (pin "3") (pinfunction "E_3") (pintype "passive"))
      (node (ref "R12") (pin "2") (pinfunction "2_2") (pintype "passive"))
      (node (ref "R13") (pin "2") (pinfunction "2_2") (pintype "passive"))
      (node (ref "R14") (pin "2") (pinfunction "2_2") (pintype "passive"))
      (node (ref "R15") (pin "2") (pinfunction "2_2") (pintype "passive"))
      (node (ref "R4") (pin "2") (pinfunction "2_2") (pintype "passive"))
      (node (ref "U1") (pin "11") (pinfunction "VSS_11") (pintype "passive"))
      (node (ref "U1") (pin "15") (pinfunction "AHL_15") (pintype "passive"))
      (node (ref "U2") (pin "14") (pinfunction "VSSA_14") (pintype "passive"))
      (node (ref "U2") (pin "31") (pinfunction "VSSIO_2_31") (pintype "passive"))
      (node (ref "U2") (pin "4") (pinfunction "VSSIO_1_4") (pintype "passive"))
      (node (ref "U2") (pin "5") (pinfunction "VSS_5") (pintype "passive"))
      (node (ref "Z1") (pin "1") (pinfunction "A_1") (pintype "passive"))
      (node (ref "Z2") (pin "1") (pinfunction "A_1") (pintype "passive"))
      (node (ref "Z3") (pin "1") (pinfunction "A_1") (pintype "passive"))
    )
    (net (code "53") (name "Net-(IC1-G1)") (class "Default")
      (node (ref "IC1") (pin "2") (pinfunction "G1_2") (pintype "passive"))
      (node (ref "Q6") (pin "2") (pinfunction "C_2") (pintype "passive"))
      (node (ref "R11") (pin "2") (pinfunction "2_2") (pintype "passive"))
      (node (ref "R12") (pin "1") (pinfunction "1_1") (pintype "passive"))
    )
    (net (code "54") (name "Net-(IC1-G2)") (class "Default")
      (node (ref "IC1") (pin "4") (pinfunction "G2_4") (pintype "passive"))
      (node (ref "Q7") (pin "2") (pinfunction "C_2") (pintype "passive"))
      (node (ref "R13") (pin "1") (pinfunction "1_1") (pintype "passive"))
      (node (ref "R16") (pin "1") (pinfunction "1_1") (pintype "passive"))
    )
    (net (code "55") (name "Net-(LED1-Pad1)") (class "Default")
      (node (ref "LED1") (pin "1") (pinfunction "1_1") (pintype "passive"))
      (node (ref "RB1") (pin "7") (pintype "passive"))
    )
    (net (code "56") (name "Net-(LED2-Pad1)") (class "Default")
      (node (ref "LED2") (pin "1") (pinfunction "1_1") (pintype "passive"))
      (node (ref "RB1") (pin "8") (pintype "passive"))
    )
    (net (code "57") (name "Net-(LED3-Pad1)") (class "Default")
      (node (ref "LED3") (pin "1") (pinfunction "1_1") (pintype "passive"))
      (node (ref "RB1") (pin "5") (pintype "passive"))
    )
    (net (code "58") (name "Net-(LED4-Pad1)") (class "Default")
      (node (ref "LED4") (pin "1") (pinfunction "1_1") (pintype "passive"))
      (node (ref "RB1") (pin "6") (pintype "passive"))
    )
    (net (code "59") (name "Net-(LED5-Pad1)") (class "Default")
      (node (ref "LED5") (pin "1") (pinfunction "1_1") (pintype "passive"))
      (node (ref "RB2") (pin "8") (pintype "passive"))
    )
    (net (code "60") (name "Net-(LED6-Pad1)") (class "Default")
      (node (ref "LED6") (pin "1") (pinfunction "1_1") (pintype "passive"))
      (node (ref "RB2") (pin "7") (pintype "passive"))
    )
    (net (code "61") (name "Net-(LED7-Pad1)") (class "Default")
      (node (ref "LED7") (pin "1") (pinfunction "1_1") (pintype "passive"))
      (node (ref "RB2") (pin "6") (pintype "passive"))
    )
    (net (code "62") (name "Net-(LED8-Pad1)") (class "Default")
      (node (ref "LED8") (pin "1") (pinfunction "1_1") (pintype "passive"))
      (node (ref "RB2") (pin "5") (pintype "passive"))
    )
    (net (code "63") (name "Net-(LED9-A)") (class "Default")
      (node (ref "LED9") (pin "1") (pinfunction "A_1") (pintype "passive"))
      (node (ref "R1") (pin "1") (pinfunction "1_1") (pintype "passive"))
    )
    (net (code "64") (name "Net-(LED10-A)") (class "Default")
      (node (ref "LED10") (pin "11") (pinfunction "A_11") (pintype "passive"))
      (node (ref "RB4") (pin "4") (pintype "passive"))
    )
    (net (code "65") (name "Net-(LED10-B)") (class "Default")
      (node (ref "LED10") (pin "7") (pinfunction "B_7") (pintype "passive"))
      (node (ref "RB4") (pin "2") (pintype "passive"))
    )
    (net (code "66") (name "Net-(LED10-C)") (class "Default")
      (node (ref "LED10") (pin "4") (pinfunction "C_4") (pintype "passive"))
      (node (ref "RB5") (pin "2") (pintype "passive"))
    )
    (net (code "67") (name "Net-(LED10-D)") (class "Default")
      (node (ref "LED10") (pin "2") (pinfunction "D_2") (pintype "passive"))
      (node (ref "RB5") (pin "4") (pintype "passive"))
    )
    (net (code "68") (name "Net-(LED10-DIG1)") (class "Default")
      (node (ref "LED10") (pin "12") (pinfunction "DIG1_12") (pintype "passive"))
      (node (ref "Q1") (pin "2") (pinfunction "C_2") (pintype "passive"))
    )
    (net (code "69") (name "Net-(LED10-DIG2)") (class "Default")
      (node (ref "LED10") (pin "9") (pinfunction "DIG2_9") (pintype "passive"))
      (node (ref "Q3") (pin "2") (pinfunction "C_2") (pintype "passive"))
    )
    (net (code "70") (name "Net-(LED10-DIG3)") (class "Default")
      (node (ref "LED10") (pin "8") (pinfunction "DIG3_8") (pintype "passive"))
      (node (ref "Q4") (pin "2") (pinfunction "C_2") (pintype "passive"))
    )
    (net (code "71") (name "Net-(LED10-DIG4)") (class "Default")
      (node (ref "LED10") (pin "6") (pinfunction "DIG4_6") (pintype "passive"))
      (node (ref "Q5") (pin "2") (pinfunction "C_2") (pintype "passive"))
    )
    (net (code "72") (name "Net-(LED10-DP)") (class "Default")
      (node (ref "LED10") (pin "3") (pinfunction "DP_3") (pintype "passive"))
      (node (ref "RB5") (pin "3") (pintype "passive"))
    )
    (net (code "73") (name "Net-(LED10-E)") (class "Default")
      (node (ref "LED10") (pin "1") (pinfunction "E_1") (pintype "passive"))
      (node (ref "RB4") (pin "1") (pintype "passive"))
    )
    (net (code "74") (name "Net-(LED10-F)") (class "Default")
      (node (ref "LED10") (pin "10") (pinfunction "F_10") (pintype "passive"))
      (node (ref "RB4") (pin "3") (pintype "passive"))
    )
    (net (code "75") (name "Net-(LED10-G)") (class "Default")
      (node (ref "LED10") (pin "5") (pinfunction "G_5") (pintype "passive"))
      (node (ref "RB5") (pin "1") (pintype "passive"))
    )
    (net (code "76") (name "Net-(LM1-OUT)") (class "Default")
      (node (ref "D_LM1") (pin "2") (pinfunction "2_2") (pintype "passive"))
      (node (ref "LM1") (pin "2") (pinfunction "OUT_2") (pintype "power_in"))
      (node (ref "L_LM1") (pin "1") (pinfunction "1_1") (pintype "passive"))
    )
    (net (code "77") (name "Net-(Q2-B)") (class "Default")
      (node (ref "Q2") (pin "1") (pinfunction "B_1") (pintype "passive"))
      (node (ref "R2") (pin "1") (pinfunction "1_1") (pintype "passive"))
    )
    (net (code "78") (name "Net-(Q2-C)") (class "Default")
      (node (ref "D1") (pin "1") (pinfunction "1_1") (pintype "passive"))
      (node (ref "LS1") (pin "2") (pinfunction "2_2") (pintype "passive"))
      (node (ref "Q2") (pin "2") (pinfunction "C_2") (pintype "passive"))
    )
    (net (code "79") (name "Net-(Q6-B)") (class "Default")
      (node (ref "Q6") (pin "1") (pinfunction "B_1") (pintype "passive"))
      (node (ref "R7") (pin "1") (pinfunction "1_1") (pintype "passive"))
    )
    (net (code "80") (name "Net-(Q7-B)") (class "Default")
      (node (ref "Q7") (pin "1") (pinfunction "B_1") (pintype "passive"))
      (node (ref "R10") (pin "1") (pinfunction "1_1") (pintype "passive"))
    )
    (net (code "81") (name "Net-(U2-VCAP)") (class "Default")
      (node (ref "C8") (pin "2") (pinfunction "2_2") (pintype "passive"))
      (node (ref "U2") (pin "6") (pinfunction "VCAP_6") (pintype "passive"))
    )
    (net (code "82") (name "Net-(Z1-K)") (class "Default")
      (node (ref "R3") (pin "1") (pinfunction "1_1") (pintype "passive"))
      (node (ref "R4") (pin "1") (pinfunction "1_1") (pintype "passive"))
      (node (ref "R5") (pin "1") (pinfunction "1_1") (pintype "passive"))
      (node (ref "Z1") (pin "2") (pinfunction "K_2") (pintype "passive"))
    )
    (net (code "83") (name "Net-(Z2-K)") (class "Default")
      (node (ref "C18") (pin "1") (pinfunction "1_1") (pintype "passive"))
      (node (ref "R15") (pin "1") (pinfunction "1_1") (pintype "passive"))
      (node (ref "R18") (pin "2") (pinfunction "2_2") (pintype "passive"))
      (node (ref "R9") (pin "2") (pinfunction "2_2") (pintype "passive"))
      (node (ref "Z2") (pin "2") (pinfunction "K_2") (pintype "passive"))
    )
    (net (code "84") (name "Net-(Z3-K)") (class "Default")
      (node (ref "C16") (pin "1") (pinfunction "1_1") (pintype "passive"))
      (node (ref "R14") (pin "1") (pinfunction "1_1") (pintype "passive"))
      (node (ref "R17") (pin "2") (pinfunction "2_2") (pintype "passive"))
      (node (ref "R8") (pin "2") (pinfunction "2_2") (pintype "passive"))
      (node (ref "Z3") (pin "2") (pinfunction "K_2") (pintype "passive"))
    )
    (net (code "85") (name "VCC") (class "Default")
      (node (ref "C11") (pin "2") (pintype "passive"))
      (node (ref "C_LM2") (pin "1") (pinfunction "1_1") (pintype "passive"))
      (node (ref "D1") (pin "2") (pinfunction "2_2") (pintype "passive"))
      (node (ref "D2") (pin "1") (pinfunction "1_1") (pintype "passive"))
      (node (ref "J1") (pin "1") (pinfunction "1_1") (pintype "passive"))
      (node (ref "LM1") (pin "4") (pinfunction "FB_4") (pintype "input"))
      (node (ref "LS1") (pin "1") (pinfunction "1_1") (pintype "passive"))
      (node (ref "L_LM1") (pin "2") (pinfunction "2_2") (pintype "passive"))
      (node (ref "Q1") (pin "3") (pinfunction "E_3") (pintype "passive"))
      (node (ref "Q3") (pin "3") (pinfunction "E_3") (pintype "passive"))
      (node (ref "Q4") (pin "3") (pinfunction "E_3") (pintype "passive"))
      (node (ref "Q5") (pin "3") (pinfunction "E_3") (pintype "passive"))
      (node (ref "R1") (pin "2") (pinfunction "2_2") (pintype "passive"))
      (node (ref "R6") (pin "1") (pinfunction "1_1") (pintype "passive"))
      (node (ref "RB1") (pin "1") (pintype "passive"))
      (node (ref "RB1") (pin "2") (pintype "passive"))
      (node (ref "RB1") (pin "3") (pintype "passive"))
      (node (ref "RB1") (pin "4") (pintype "passive"))
      (node (ref "RB2") (pin "1") (pintype "passive"))
      (node (ref "RB2") (pin "2") (pintype "passive"))
      (node (ref "RB2") (pin "3") (pintype "passive"))
      (node (ref "RB2") (pin "4") (pintype "passive"))
    )
    (net (code "86") (name "VCC_MCU") (class "Default")
      (node (ref "C1") (pin "2") (pinfunction "2_2") (pintype "passive"))
      (node (ref "C10") (pin "1") (pinfunction "1_1") (pintype "passive"))
      (node (ref "C12") (pin "1") (pinfunction "1_1") (pintype "passive"))
      (node (ref "C9") (pin "1") (pinfunction "1_1") (pintype "passive"))
      (node (ref "D2") (pin "2") (pinfunction "2_2") (pintype "passive"))
      (node (ref "U2") (pin "13") (pinfunction "VDDA_13") (pintype "passive"))
      (node (ref "U2") (pin "32") (pinfunction "VDDIO_2_32") (pintype "passive"))
      (node (ref "U2") (pin "7") (pinfunction "VDD_7") (pintype "passive"))
      (node (ref "U2") (pin "8") (pinfunction "VDDIO_1_8") (pintype "passive"))
    )
    (net (code "87") (name "unconnected-(U1-0PS1-Pad13)") (class "Default")
      (node (ref "U1") (pin "13") (pinfunction "0PS1_13") (pintype "passive"))
    )
    (net (code "88") (name "unconnected-(U1-DV-Pad24)") (class "Default")
      (node (ref "U1") (pin "24") (pinfunction "DV_24") (pintype "passive"))
    )
    (net (code "89") (name "unconnected-(U1-I4-Pad5)") (class "Default")
      (node (ref "U1") (pin "5") (pinfunction "I4_5") (pintype "passive"))
    )
    (net (code "90") (name "unconnected-(U1-I5-Pad4)") (class "Default")
      (node (ref "U1") (pin "4") (pinfunction "I5_4") (pintype "passive"))
    )
    (net (code "91") (name "unconnected-(U1-I6-Pad3)") (class "Default")
      (node (ref "U1") (pin "3") (pinfunction "I6_3") (pintype "passive"))
    )
    (net (code "92") (name "unconnected-(U1-I7-Pad2)") (class "Default")
      (node (ref "U1") (pin "2") (pinfunction "I7_2") (pintype "passive"))
    )
    (net (code "93") (name "unconnected-(U1-OCS1-Pad10)") (class "Default")
      (node (ref "U1") (pin "10") (pinfunction "OCS1_10") (pintype "passive"))
    )
    (net (code "94") (name "unconnected-(U1-OPS0-Pad14)") (class "Default")
      (node (ref "U1") (pin "14") (pinfunction "OPS0_14") (pintype "passive"))
    )
    (net (code "95") (name "unconnected-(U1-OSC{slash}TOPAD-Pad1)") (class "Default")
      (node (ref "U1") (pin "1") (pinfunction "OSC/TOPAD_1") (pintype "passive"))
    )
    (net (code "96") (name "unconnected-(U1-Q4-Pad20)") (class "Default")
      (node (ref "U1") (pin "20") (pinfunction "Q4_20") (pintype "passive"))
    )
    (net (code "97") (name "unconnected-(U1-Q5-Pad21)") (class "Default")
      (node (ref "U1") (pin "21") (pinfunction "Q5_21") (pintype "passive"))
    )
    (net (code "98") (name "unconnected-(U1-Q6-Pad22)") (class "Default")
      (node (ref "U1") (pin "22") (pinfunction "Q6_22") (pintype "passive"))
    )
    (net (code "99") (name "unconnected-(U1-Q7-Pad23)") (class "Default")
      (node (ref "U1") (pin "23") (pinfunction "Q7_23") (pintype "passive"))
    )
    (net (code "100") (name "unconnected-(U1-SLSE1-Pad25)") (class "Default")
      (node (ref "U1") (pin "25") (pinfunction "SLSE1_25") (pintype "passive"))
    )
    (net (code "101") (name "unconnected-(U1-SLSE2-Pad26)") (class "Default")
      (node (ref "U1") (pin "26") (pinfunction "SLSE2_26") (pintype "passive"))
    )
    (net (code "102") (name "unconnected-(U1-SLSE3-Pad27)") (class "Default")
      (node (ref "U1") (pin "27") (pinfunction "SLSE3_27") (pintype "passive"))
    )
    (net (code "103") (name "unconnected-(U1-SLSE4-Pad28)") (class "Default")
      (node (ref "U1") (pin "28") (pinfunction "SLSE4_28") (pintype "passive"))
    )
    (net (code "104") (name "unconnected-(U2-PE0(HS){slash}CLK_CCO-Pad40)") (class "Default")
      (node (ref "U2") (pin "40") (pinfunction "PE0(HS)/CLK_CCO_40") (pintype "passive"))
    )
    (net (code "105") (name "unconnected-(U2-PE1(T){slash}I2C_SCL-Pad39)") (class "Default")
      (node (ref "U2") (pin "39") (pinfunction "PE1(T)/I2C_SCL_39") (pintype "passive+no_connect"))
    )
    (net (code "106") (name "unconnected-(U2-PE2(T){slash}I2C_SDA-Pad38)") (class "Default")
      (node (ref "U2") (pin "38") (pinfunction "PE2(T)/I2C_SDA_38") (pintype "passive+no_connect"))
    )
  )
)
